# LC_LPF_PI.net
KiCad netlist of a schematic drawn in Altium Designer
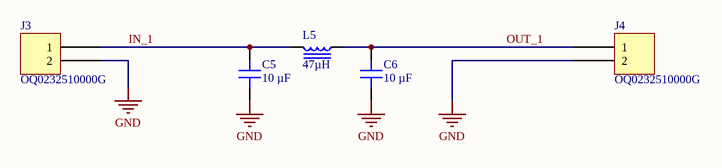
[diagram p0: LC_LPF_PI.SchDoc]

(export (version "E")
  (design (tool "Eeschema 10.0.6"))
  (components
    (comp (ref "C5")
      (value "10 µF")
      (footprint "CAP 0603_1608")
      (description "CAP CER 10UF 10V X5R 0603")
      (fields
        (field (name "PART NUMBER") "MD0603BW106M100NHT-EM")
        (field (name "MANUFACTURER") "Knowles Novacap")
      )
      (libsource (lib "Celestial Altium Library - altium_library") (part "Capacitor"))
    )
    (comp (ref "C6")
      (value "10 µF")
      (footprint "CAP 0603_1608")
      (description "CAP CER 10UF 10V X5R 0603")
      (fields
        (field (name "PART NUMBER") "MD0603BW106M100NHT-EM")
        (field (name "MANUFACTURER") "Knowles Novacap")
      )
      (libsource (lib "Celestial Altium Library - altium_library") (part "Capacitor"))
    )
    (comp (ref "J3")
      (value "OQ0232510000G")
      (footprint "FCI 06-381-2PIN")
      (description "TERM BLOCK HDR 2POS 90DEG 3.81MM")
      (fields (field (name "MANUFACTURER") "Amphenol Anytek"))
      (libsource (lib "") (part "2 Pin_1"))
    )
    (comp (ref "J4")
      (value "OQ0232510000G")
      (footprint "FCI 06-381-2PIN")
      (description "TERM BLOCK HDR 2POS 90DEG 3.81MM")
      (fields (field (name "MANUFACTURER") "Amphenol Anytek"))
      (libsource (lib "Celestial Altium Library - altium_library") (part "2 Pin"))
    )
    (comp (ref "L5")
      (value "47µH")
      (footprint "IND 0603_1608 RF WW")
      (description "INDUCTORPOWER LINE 0603 47H 20%")
      (fields (field (name "PART NUMBER") "L0603B470MPWFT") (field (name "MANUFACTURER") "KEMET"))
      (libsource (lib "Celestial Altium Library - altium_library") (part "Inductor"))
    )
  )
  (nets
    (net (code "1") (name "/IN_1") (class "Default")
      (node (ref "C5") (pin "2") (pinfunction "2_2") (pintype "passive"))
      (node (ref "J3") (pin "1") (pinfunction "1_1") (pintype "passive"))
      (node (ref "L5") (pin "2") (pinfunction "2_2") (pintype "passive"))
    )
    (net (code "2") (name "/OUT_1") (class "Default")
      (node (ref "C6") (pin "2") (pinfunction "2_2") (pintype "passive"))
      (node (ref "J4") (pin "1") (pinfunction "1_1") (pintype "passive"))
      (node (ref "L5") (pin "1") (pinfunction "1_1") (pintype "passive"))
    )
    (net (code "3") (name "GND") (class "Default")
      (node (ref "C5") (pin "1") (pinfunction "1_1") (pintype "passive"))
      (node (ref "C6") (pin "1") (pinfunction "1_1") (pintype "passive"))
      (node (ref "J3") (pin "2") (pinfunction "2_2") (pintype "passive"))
      (node (ref "J4") (pin "2") (pinfunction "2_2") (pintype "passive"))
    )
  )
)
